# Schematic.net
KiCad netlist of a schematic drawn in Altium Designer
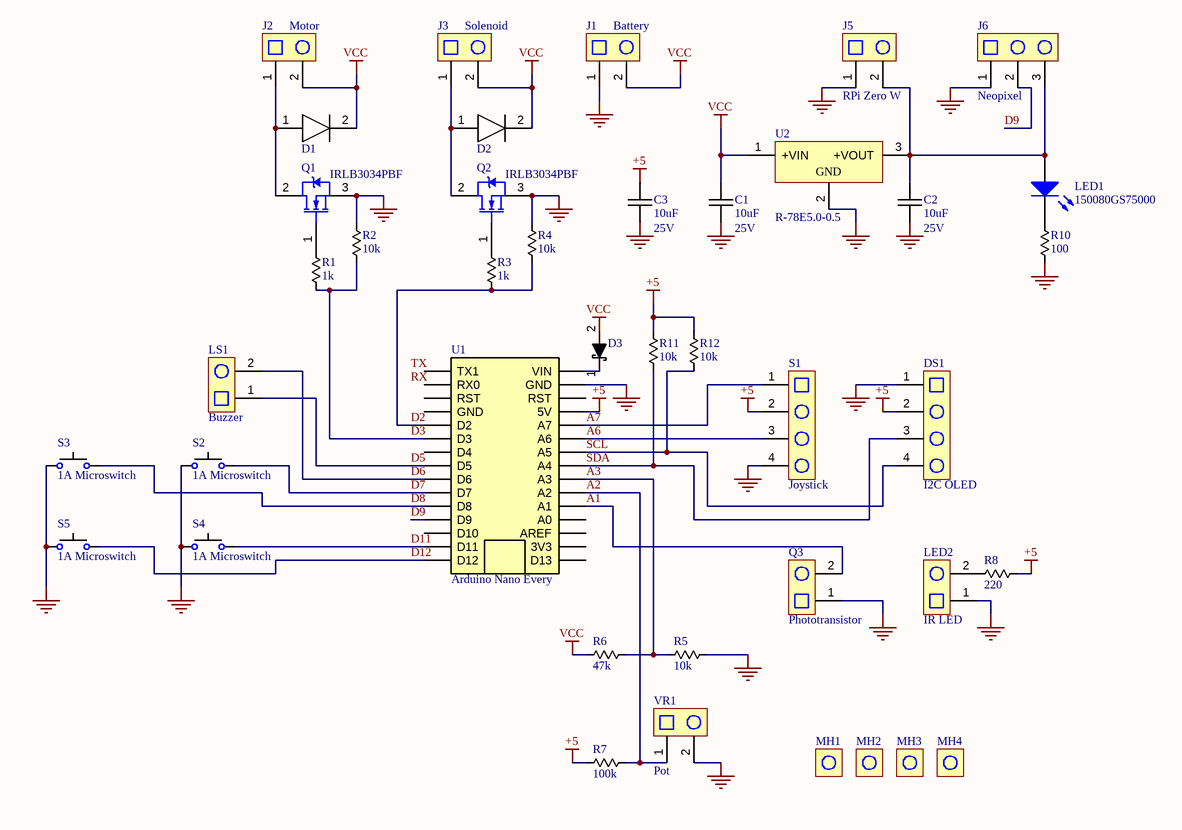
[diagram p0: Schematic.SchDoc]

(export (version "E")
  (design (tool "Eeschema 10.0.6"))
  (components
    (comp (ref "C1")
      (value "10uF")
      (footprint "chip_0805")
      (description "CAP, 10uF, 10%, 25V, X7R, 0805")
      (fields
        (field (name "PART NUMBER") "CAP-00131")
        (field (name "TOLERANCE") "10%")
        (field (name "VOLTAGE RATING") "25V")
      )
      (libsource (lib "Capacitors$") (part "CAP-00131"))
    )
    (comp (ref "C2")
      (value "10uF")
      (footprint "chip_0805")
      (description "CAP, 10uF, 10%, 25V, X7R, 0805")
      (fields
        (field (name "PART NUMBER") "CAP-00131")
        (field (name "TOLERANCE") "10%")
        (field (name "VOLTAGE RATING") "25V")
      )
      (libsource (lib "Capacitors$") (part "CAP-00131"))
    )
    (comp (ref "C3")
      (value "10uF")
      (footprint "chip_0805")
      (description "CAP, 10uF, 10%, 25V, X7R, 0805")
      (fields
        (field (name "PART NUMBER") "CAP-00131")
        (field (name "TOLERANCE") "10%")
        (field (name "VOLTAGE RATING") "25V")
      )
      (libsource (lib "Capacitors$") (part "CAP-00131"))
    )
    (comp (ref "D1")
      (value "Diode Thru-Hole 0.5\"")
      (footprint "D-1")
      (libsource (lib "Rapidstrike Mod Components Lib") (part "D-1"))
    )
    (comp (ref "D2")
      (value "Diode Thru-Hole 0.5\"")
      (footprint "D-1")
      (libsource (lib "Rapidstrike Mod Components Lib") (part "D-1"))
    )
    (comp (ref "D3")
      (value "MBRA340T3G")
      (footprint "do-214ac")
      (description "Dio Shtky, 3A, 0.45V, 40V, SMA")
      (fields (field (name "PART NUMBER") "DIO-00005") (field (name "MANUFACTURER") "ON Semi"))
      (libsource (lib "Diodes$") (part "DIO-00005"))
    )
    (comp (ref "DS1")
      (value "I2C OLED")
      (footprint "J-5")
      (description "4 pin Thru-Hole AWG 24")
      (libsource (lib "Rapidstrike Mod Components Lib") (part "J-5"))
    )
    (comp (ref "J1")
      (value "Battery")
      (footprint "J-6-LONG")
      (description "2 pin Thru-Hole AWG 16 Larger Spacing")
      (libsource (lib "Rapidstrike Mod Components Lib") (part "J-6-LONG"))
    )
    (comp (ref "J2")
      (value "Motor")
      (footprint "J-6")
      (description "2 pin Thru-Hole AWG 16")
      (libsource (lib "Rapidstrike Mod Components Lib") (part "J-6"))
    )
    (comp (ref "J3")
      (value "Solenoid")
      (footprint "J-6")
      (description "2 pin Thru-Hole AWG 16")
      (libsource (lib "Rapidstrike Mod Components Lib") (part "J-6"))
    )
    (comp (ref "J5")
      (value "RPi Zero W")
      (footprint "J-3")
      (description "2 pin Thru-Hole AWG 24")
      (libsource (lib "") (part "J-3_1"))
    )
    (comp (ref "J6")
      (value "Neopixel")
      (footprint "J-4")
      (description "3 pin Thru-Hole AWG 24")
      (libsource (lib "Rapidstrike Mod Components Lib") (part "J-4"))
    )
    (comp (ref "LED1")
      (value "150080GS75000")
      (footprint "0805_A")
      (description "SMD mono-color Chip LED, WL-SMCW, Green")
      (fields (field (name "MANUFACTURER") "Wuerth Elektronik"))
      (libsource (lib "Altium Content Vault") (part "WE-LED_K1A2-2"))
    )
    (comp (ref "LED2")
      (value "IR LED")
      (footprint "J-3")
      (description "2 pin Thru-Hole AWG 24")
      (libsource (lib "Rapidstrike Mod Components Lib") (part "J-3"))
    )
    (comp (ref "LS1")
      (value "Buzzer")
      (footprint "J-3")
      (description "2 pin Thru-Hole AWG 24")
      (libsource (lib "Rapidstrike Mod Components Lib") (part "J-3"))
    )
    (comp (ref "MH1")
      (value "MH-1")
      (footprint "MH-1")
      (description "Mouting Hole M2.5")
      (libsource (lib "Rapidstrike Mod Components Lib") (part "MH-1"))
    )
    (comp (ref "MH2")
      (value "MH-1")
      (footprint "MH-1")
      (description "Mouting Hole M2.5")
      (libsource (lib "Rapidstrike Mod Components Lib") (part "MH-1"))
    )
    (comp (ref "MH3")
      (value "MH-1")
      (footprint "MH-1")
      (description "Mouting Hole M2.5")
      (libsource (lib "Rapidstrike Mod Components Lib") (part "MH-1"))
    )
    (comp (ref "MH4")
      (value "MH-1")
      (footprint "MH-1")
      (description "Mouting Hole M2.5")
      (libsource (lib "Rapidstrike Mod Components Lib") (part "MH-1"))
    )
    (comp (ref "Q1")
      (value "IRLB3034PBF")
      (footprint "INF-PG-TO-220AB")
      (description "Mosfet N-Channel, 40 V, 195 A, -55 to 175 degC, 3-Pin TO-220AB, RoHS, Tube")
      (fields (field (name "MANUFACTURER") "International Rectifier"))
      (libsource (lib "Altium Content Vault") (part "NEMOS-GDS-3_B"))
    )
    (comp (ref "Q2")
      (value "IRLB3034PBF")
      (footprint "INF-PG-TO-220AB")
      (description "Mosfet N-Channel, 40 V, 195 A, -55 to 175 degC, 3-Pin TO-220AB, RoHS, Tube")
      (fields (field (name "MANUFACTURER") "International Rectifier"))
      (libsource (lib "Altium Content Vault") (part "NEMOS-GDS-3_B"))
    )
    (comp (ref "Q3")
      (value "Phototransistor")
      (footprint "J-3")
      (description "2 pin Thru-Hole AWG 24")
      (libsource (lib "Rapidstrike Mod Components Lib") (part "J-3"))
    )
    (comp (ref "R1")
      (value "1k")
      (footprint "chip_0805")
      (description "RES SMD 1K OHM 1% 1/8W 0805")
      (fields (field (name "PART NUMBER") "RES-00361") (field (name "TOLERANCE") "1%"))
      (libsource (lib "Resistors$") (part "RES-00361"))
    )
    (comp (ref "R2")
      (value "10k")
      (footprint "chip_0805")
      (description "RES SMD 10K OHM 1% 1/8W 0805")
      (fields (field (name "PART NUMBER") "RES-00307") (field (name "TOLERANCE") "1%"))
      (libsource (lib "Resistors$") (part "RES-00307"))
    )
    (comp (ref "R3")
      (value "1k")
      (footprint "chip_0805")
      (description "RES SMD 1K OHM 1% 1/8W 0805")
      (fields (field (name "PART NUMBER") "RES-00361") (field (name "TOLERANCE") "1%"))
      (libsource (lib "Resistors$") (part "RES-00361"))
    )
    (comp (ref "R4")
      (value "10k")
      (footprint "chip_0805")
      (description "RES SMD 10K OHM 1% 1/8W 0805")
      (fields (field (name "PART NUMBER") "RES-00307") (field (name "TOLERANCE") "1%"))
      (libsource (lib "Resistors$") (part "RES-00307"))
    )
    (comp (ref "R5")
      (value "10k")
      (footprint "chip_0805")
      (description "RES SMD 10K OHM 1% 1/8W 0805")
      (fields (field (name "PART NUMBER") "RES-00307") (field (name "TOLERANCE") "1%"))
      (libsource (lib "Resistors$") (part "RES-00307"))
    )
    (comp (ref "R6")
      (value "47k")
      (footprint "chip_0805")
      (description "RES SMD 47K OHM 1% 1/8W 0805")
      (fields (field (name "PART NUMBER") "RES-00493") (field (name "TOLERANCE") "1%"))
      (libsource (lib "Resistors$") (part "RES-00493"))
    )
    (comp (ref "R7")
      (value "100k")
      (footprint "axial_0.3")
      (description "RES THT 100K OHM 1% 1/4W 0.3\" AXIAL")
      (fields (field (name "PART NUMBER") "RES-00609") (field (name "TOLERANCE") "1%"))
      (libsource (lib "Resistors$") (part "RES-00609"))
    )
    (comp (ref "R8")
      (value "220")
      (footprint "chip_0805")
      (description "RES SMD 220 OHM 1% 1/8W 0805")
      (fields (field (name "PART NUMBER") "RES-00202") (field (name "TOLERANCE") "1%"))
      (libsource (lib "Resistors$") (part "RES-00202"))
    )
    (comp (ref "R10")
      (value "100")
      (footprint "chip_0805")
      (description "RES SMD 100 OHM 1% 1/8W 0805")
      (fields (field (name "PART NUMBER") "RES-00179") (field (name "TOLERANCE") "1%"))
      (libsource (lib "Resistors$") (part "RES-00179"))
    )
    (comp (ref "R11")
      (value "10k")
      (footprint "chip_0805")
      (description "RES SMD 10K OHM 1% 1/8W 0805")
      (fields (field (name "PART NUMBER") "RES-00307") (field (name "TOLERANCE") "1%"))
      (libsource (lib "Resistors$") (part "RES-00307"))
    )
    (comp (ref "R12")
      (value "10k")
      (footprint "chip_0805")
      (description "RES SMD 10K OHM 1% 1/8W 0805")
      (fields (field (name "PART NUMBER") "RES-00307") (field (name "TOLERANCE") "1%"))
      (libsource (lib "Resistors$") (part "RES-00307"))
    )
    (comp (ref "S1")
      (value "Joystick")
      (footprint "J-5")
      (description "4 pin Thru-Hole AWG 24")
      (libsource (lib "Rapidstrike Mod Components Lib") (part "J-5"))
    )
    (comp (ref "S2")
      (value "1A Microswitch")
      (footprint "J-3")
      (libsource (lib "Rapidstrike Mod Components Lib") (part "S-1"))
    )
    (comp (ref "S3")
      (value "1A Microswitch")
      (footprint "J-3")
      (libsource (lib "Rapidstrike Mod Components Lib") (part "S-1"))
    )
    (comp (ref "S4")
      (value "1A Microswitch")
      (footprint "J-3")
      (libsource (lib "Rapidstrike Mod Components Lib") (part "S-1"))
    )
    (comp (ref "S5")
      (value "1A Microswitch")
      (footprint "J-3")
      (libsource (lib "Rapidstrike Mod Components Lib") (part "S-1"))
    )
    (comp (ref "U1")
      (value "Arduino Nano Every")
      (footprint "ARDUINO_NANO")
      (description "Arduino Nano Every, SMD Footprint")
      (libsource (lib "Rapidstrike Mod Components Lib") (part "U-1"))
    )
    (comp (ref "U2")
      (value "R-78E5.0-0.5")
      (footprint "REPO-R-78E-0.5-3_V")
      (description "DC/DC-Converter, 5 V Single Output, 500 mA, -40 to 85 degC, 3-Pin THD, RoHS, Tube")
      (fields (field (name "MANUFACTURER") "Recom Power"))
      (libsource (lib "Altium Content Vault") (part "REPO-R-78XX-3"))
    )
    (comp (ref "VR1")
      (value "Pot")
      (footprint "J-3")
      (description "2 pin Thru-Hole AWG 24")
      (libsource (lib "") (part "J-3_1"))
    )
  )
  (nets
    (net (code "1") (name "+5") (class "Default")
      (node (ref "C3") (pin "1") (pinfunction "1_1") (pintype "passive"))
      (node (ref "DS1") (pin "2") (pinfunction "2_2") (pintype "passive"))
      (node (ref "R11") (pin "2") (pinfunction "2_2") (pintype "passive"))
      (node (ref "R12") (pin "2") (pinfunction "2_2") (pintype "passive"))
      (node (ref "R7") (pin "1") (pinfunction "1_1") (pintype "passive"))
      (node (ref "R8") (pin "1") (pinfunction "1_1") (pintype "passive"))
      (node (ref "S1") (pin "2") (pinfunction "2_2") (pintype "passive"))
      (node (ref "U1") (pin "27") (pinfunction "5V_27") (pintype "passive"))
    )
    (net (code "2") (name "/A1") (class "Default")
      (node (ref "Q3") (pin "2") (pinfunction "2_2") (pintype "passive"))
      (node (ref "U1") (pin "20") (pinfunction "A1_20") (pintype "passive"))
    )
    (net (code "3") (name "/A2") (class "Default")
      (node (ref "R7") (pin "2") (pinfunction "2_2") (pintype "passive"))
      (node (ref "U1") (pin "21") (pinfunction "A2_21") (pintype "passive"))
      (node (ref "VR1") (pin "1") (pinfunction "1_1") (pintype "passive"))
    )
    (net (code "4") (name "/A3") (class "Default")
      (node (ref "R5") (pin "1") (pinfunction "1_1") (pintype "passive"))
      (node (ref "R6") (pin "2") (pinfunction "2_2") (pintype "passive"))
      (node (ref "U1") (pin "22") (pinfunction "A3_22") (pintype "passive"))
    )
    (net (code "5") (name "/A6") (class "Default")
      (node (ref "S1") (pin "3") (pinfunction "3_3") (pintype "passive"))
      (node (ref "U1") (pin "25") (pinfunction "A6_25") (pintype "passive"))
    )
    (net (code "6") (name "/A7") (class "Default")
      (node (ref "S1") (pin "1") (pinfunction "1_1") (pintype "passive"))
      (node (ref "U1") (pin "26") (pinfunction "A7_26") (pintype "passive"))
    )
    (net (code "7") (name "/D2") (class "Default")
      (node (ref "R3") (pin "2") (pinfunction "2_2") (pintype "passive"))
      (node (ref "R4") (pin "2") (pinfunction "2_2") (pintype "passive"))
      (node (ref "U1") (pin "5") (pinfunction "D2_5") (pintype "passive"))
    )
    (net (code "8") (name "/D3") (class "Default")
      (node (ref "R1") (pin "2") (pinfunction "2_2") (pintype "passive"))
      (node (ref "R2") (pin "2") (pinfunction "2_2") (pintype "passive"))
      (node (ref "U1") (pin "6") (pinfunction "D3_6") (pintype "passive"))
    )
    (net (code "9") (name "/D5") (class "Default")
      (node (ref "LS1") (pin "1") (pinfunction "1_1") (pintype "passive"))
      (node (ref "U1") (pin "8") (pinfunction "D5_8") (pintype "passive"))
    )
    (net (code "10") (name "/D6") (class "Default")
      (node (ref "LS1") (pin "2") (pinfunction "2_2") (pintype "passive"))
      (node (ref "U1") (pin "9") (pinfunction "D6_9") (pintype "passive"))
    )
    (net (code "11") (name "/D7") (class "Default")
      (node (ref "S2") (pin "2") (pinfunction "2_2") (pintype "passive"))
      (node (ref "U1") (pin "10") (pinfunction "D7_10") (pintype "passive"))
    )
    (net (code "12") (name "/D8") (class "Default")
      (node (ref "S3") (pin "2") (pinfunction "2_2") (pintype "passive"))
      (node (ref "U1") (pin "11") (pinfunction "D8_11") (pintype "passive"))
    )
    (net (code "13") (name "/D9") (class "Default")
      (node (ref "J6") (pin "2") (pinfunction "2_2") (pintype "passive"))
      (node (ref "U1") (pin "12") (pinfunction "D9_12") (pintype "passive"))
    )
    (net (code "14") (name "/D11") (class "Default")
      (node (ref "S4") (pin "2") (pinfunction "2_2") (pintype "passive"))
      (node (ref "U1") (pin "14") (pinfunction "D11_14") (pintype "passive"))
    )
    (net (code "15") (name "/D12") (class "Default")
      (node (ref "S5") (pin "2") (pinfunction "2_2") (pintype "passive"))
      (node (ref "U1") (pin "15") (pinfunction "D12_15") (pintype "passive"))
    )
    (net (code "17") (name "/SCL") (class "Default")
      (node (ref "DS1") (pin "4") (pinfunction "4_4") (pintype "passive"))
      (node (ref "R12") (pin "1") (pinfunction "1_1") (pintype "passive"))
      (node (ref "U1") (pin "24") (pinfunction "A5_24") (pintype "passive"))
    )
    (net (code "18") (name "/SDA") (class "Default")
      (node (ref "DS1") (pin "3") (pinfunction "3_3") (pintype "passive"))
      (node (ref "R11") (pin "1") (pinfunction "1_1") (pintype "passive"))
      (node (ref "U1") (pin "23") (pinfunction "A4_23") (pintype "passive"))
    )
    (net (code "20") (name "GND") (class "Default")
      (node (ref "C1") (pin "2") (pinfunction "2_2") (pintype "passive"))
      (node (ref "C2") (pin "2") (pinfunction "2_2") (pintype "passive"))
      (node (ref "C3") (pin "2") (pinfunction "2_2") (pintype "passive"))
      (node (ref "DS1") (pin "1") (pinfunction "1_1") (pintype "passive"))
      (node (ref "J1") (pin "1") (pinfunction "1_1") (pintype "passive"))
      (node (ref "J5") (pin "1") (pinfunction "1_1") (pintype "passive"))
      (node (ref "J6") (pin "1") (pinfunction "1_1") (pintype "passive"))
      (node (ref "LED2") (pin "1") (pinfunction "1_1") (pintype "passive"))
      (node (ref "Q1") (pin "3") (pinfunction "S_3") (pintype "passive"))
      (node (ref "Q2") (pin "3") (pinfunction "S_3") (pintype "passive"))
      (node (ref "Q3") (pin "1") (pinfunction "1_1") (pintype "passive"))
      (node (ref "R10") (pin "2") (pinfunction "2_2") (pintype "passive"))
      (node (ref "R2") (pin "1") (pinfunction "1_1") (pintype "passive"))
      (node (ref "R4") (pin "1") (pinfunction "1_1") (pintype "passive"))
      (node (ref "R5") (pin "2") (pinfunction "2_2") (pintype "passive"))
      (node (ref "S1") (pin "4") (pinfunction "4_4") (pintype "passive"))
      (node (ref "S2") (pin "1") (pinfunction "1_1") (pintype "passive"))
      (node (ref "S3") (pin "1") (pinfunction "1_1") (pintype "passive"))
      (node (ref "S4") (pin "1") (pinfunction "1_1") (pintype "passive"))
      (node (ref "S5") (pin "1") (pinfunction "1_1") (pintype "passive"))
      (node (ref "U1") (pin "29") (pinfunction "GND_29") (pintype "passive"))
      (node (ref "U2") (pin "2") (pinfunction "GND_2") (pintype "power_in"))
      (node (ref "VR1") (pin "2") (pinfunction "2_2") (pintype "passive"))
    )
    (net (code "21") (name "Net-(D1-+)") (class "Default")
      (node (ref "D1") (pin "1") (pinfunction "+_1") (pintype "passive"))
      (node (ref "J2") (pin "1") (pinfunction "1_1") (pintype "passive"))
      (node (ref "Q1") (pin "2") (pinfunction "D_2") (pintype "passive"))
    )
    (net (code "22") (name "Net-(D2-+)") (class "Default")
      (node (ref "D2") (pin "1") (pinfunction "+_1") (pintype "passive"))
      (node (ref "J3") (pin "1") (pinfunction "1_1") (pintype "passive"))
      (node (ref "Q2") (pin "2") (pinfunction "D_2") (pintype "passive"))
    )
    (net (code "23") (name "Net-(LED1-A)") (class "Default")
      (node (ref "C2") (pin "1") (pinfunction "1_1") (pintype "passive"))
      (node (ref "J5") (pin "2") (pinfunction "2_2") (pintype "passive"))
      (node (ref "J6") (pin "3") (pinfunction "3_3") (pintype "passive"))
      (node (ref "LED1") (pin "2") (pinfunction "A_2") (pintype "passive"))
      (node (ref "U2") (pin "3") (pinfunction "+VOUT_3") (pintype "power_in"))
    )
    (net (code "24") (name "Net-(LED1-K)") (class "Default")
      (node (ref "LED1") (pin "1") (pinfunction "K_1") (pintype "passive"))
      (node (ref "R10") (pin "1") (pinfunction "1_1") (pintype "passive"))
    )
    (net (code "25") (name "Net-(LED2-Pad2)") (class "Default")
      (node (ref "LED2") (pin "2") (pinfunction "2_2") (pintype "passive"))
      (node (ref "R8") (pin "2") (pinfunction "2_2") (pintype "passive"))
    )
    (net (code "26") (name "Net-(Q1-G)") (class "Default")
      (node (ref "Q1") (pin "1") (pinfunction "G_1") (pintype "passive"))
      (node (ref "R1") (pin "1") (pinfunction "1_1") (pintype "passive"))
    )
    (net (code "27") (name "Net-(Q2-G)") (class "Default")
      (node (ref "Q2") (pin "1") (pinfunction "G_1") (pintype "passive"))
      (node (ref "R3") (pin "1") (pinfunction "1_1") (pintype "passive"))
    )
    (net (code "28") (name "Net-(U1-VIN)") (class "Default")
      (node (ref "D3") (pin "1") (pinfunction "1_1") (pintype "passive"))
      (node (ref "U1") (pin "30") (pinfunction "VIN_30") (pintype "passive"))
    )
    (net (code "29") (name "VCC") (class "Default")
      (node (ref "C1") (pin "1") (pinfunction "1_1") (pintype "passive"))
      (node (ref "D1") (pin "2") (pinfunction "-_2") (pintype "passive"))
      (node (ref "D2") (pin "2") (pinfunction "-_2") (pintype "passive"))
      (node (ref "D3") (pin "2") (pinfunction "2_2") (pintype "passive"))
      (node (ref "J1") (pin "2") (pinfunction "2_2") (pintype "passive"))
      (node (ref "J2") (pin "2") (pinfunction "2_2") (pintype "passive"))
      (node (ref "J3") (pin "2") (pinfunction "2_2") (pintype "passive"))
      (node (ref "R6") (pin "1") (pinfunction "1_1") (pintype "passive"))
      (node (ref "U2") (pin "1") (pinfunction "+VIN_1") (pintype "power_in"))
    )
    (net (code "30") (name "unconnected-(U1-3V3-Pad17)") (class "Default")
      (node (ref "U1") (pin "17") (pinfunction "3V3_17") (pintype "passive"))
    )
    (net (code "31") (name "unconnected-(U1-A0-Pad19)") (class "Default")
      (node (ref "U1") (pin "19") (pinfunction "A0_19") (pintype "passive"))
    )
    (net (code "32") (name "unconnected-(U1-AREF-Pad18)") (class "Default")
      (node (ref "U1") (pin "18") (pinfunction "AREF_18") (pintype "passive"))
    )
    (net (code "33") (name "unconnected-(U1-D4-Pad7)") (class "Default")
      (node (ref "U1") (pin "7") (pinfunction "D4_7") (pintype "passive"))
    )
    (net (code "34") (name "unconnected-(U1-D10-Pad13)") (class "Default")
      (node (ref "U1") (pin "13") (pinfunction "D10_13") (pintype "passive"))
    )
    (net (code "35") (name "unconnected-(U1-D13-Pad16)") (class "Default")
      (node (ref "U1") (pin "16") (pinfunction "D13_16") (pintype "passive"))
    )
    (net (code "36") (name "unconnected-(U1-GND-Pad4)") (class "Default")
      (node (ref "U1") (pin "4") (pinfunction "GND_4") (pintype "passive"))
    )
    (net (code "37") (name "unconnected-(U1-RST-Pad3)") (class "Default")
      (node (ref "U1") (pin "3") (pinfunction "RST_3") (pintype "passive"))
    )
    (net (code "38") (name "unconnected-(U1-RST-Pad28)") (class "Default")
      (node (ref "U1") (pin "28") (pinfunction "RST_28") (pintype "passive"))
    )
    (net (code "39") (name "unconnected-(U1-RX0-Pad2)") (class "Default")
      (node (ref "U1") (pin "2") (pinfunction "RX0_2") (pintype "passive"))
    )
    (net (code "40") (name "unconnected-(U1-TX1-Pad1)") (class "Default")
      (node (ref "U1") (pin "1") (pinfunction "TX1_1") (pintype "passive"))
    )
  )
)
